# Light-ControllerV3_15.net
KiCad netlist of a schematic drawn in EAGLE
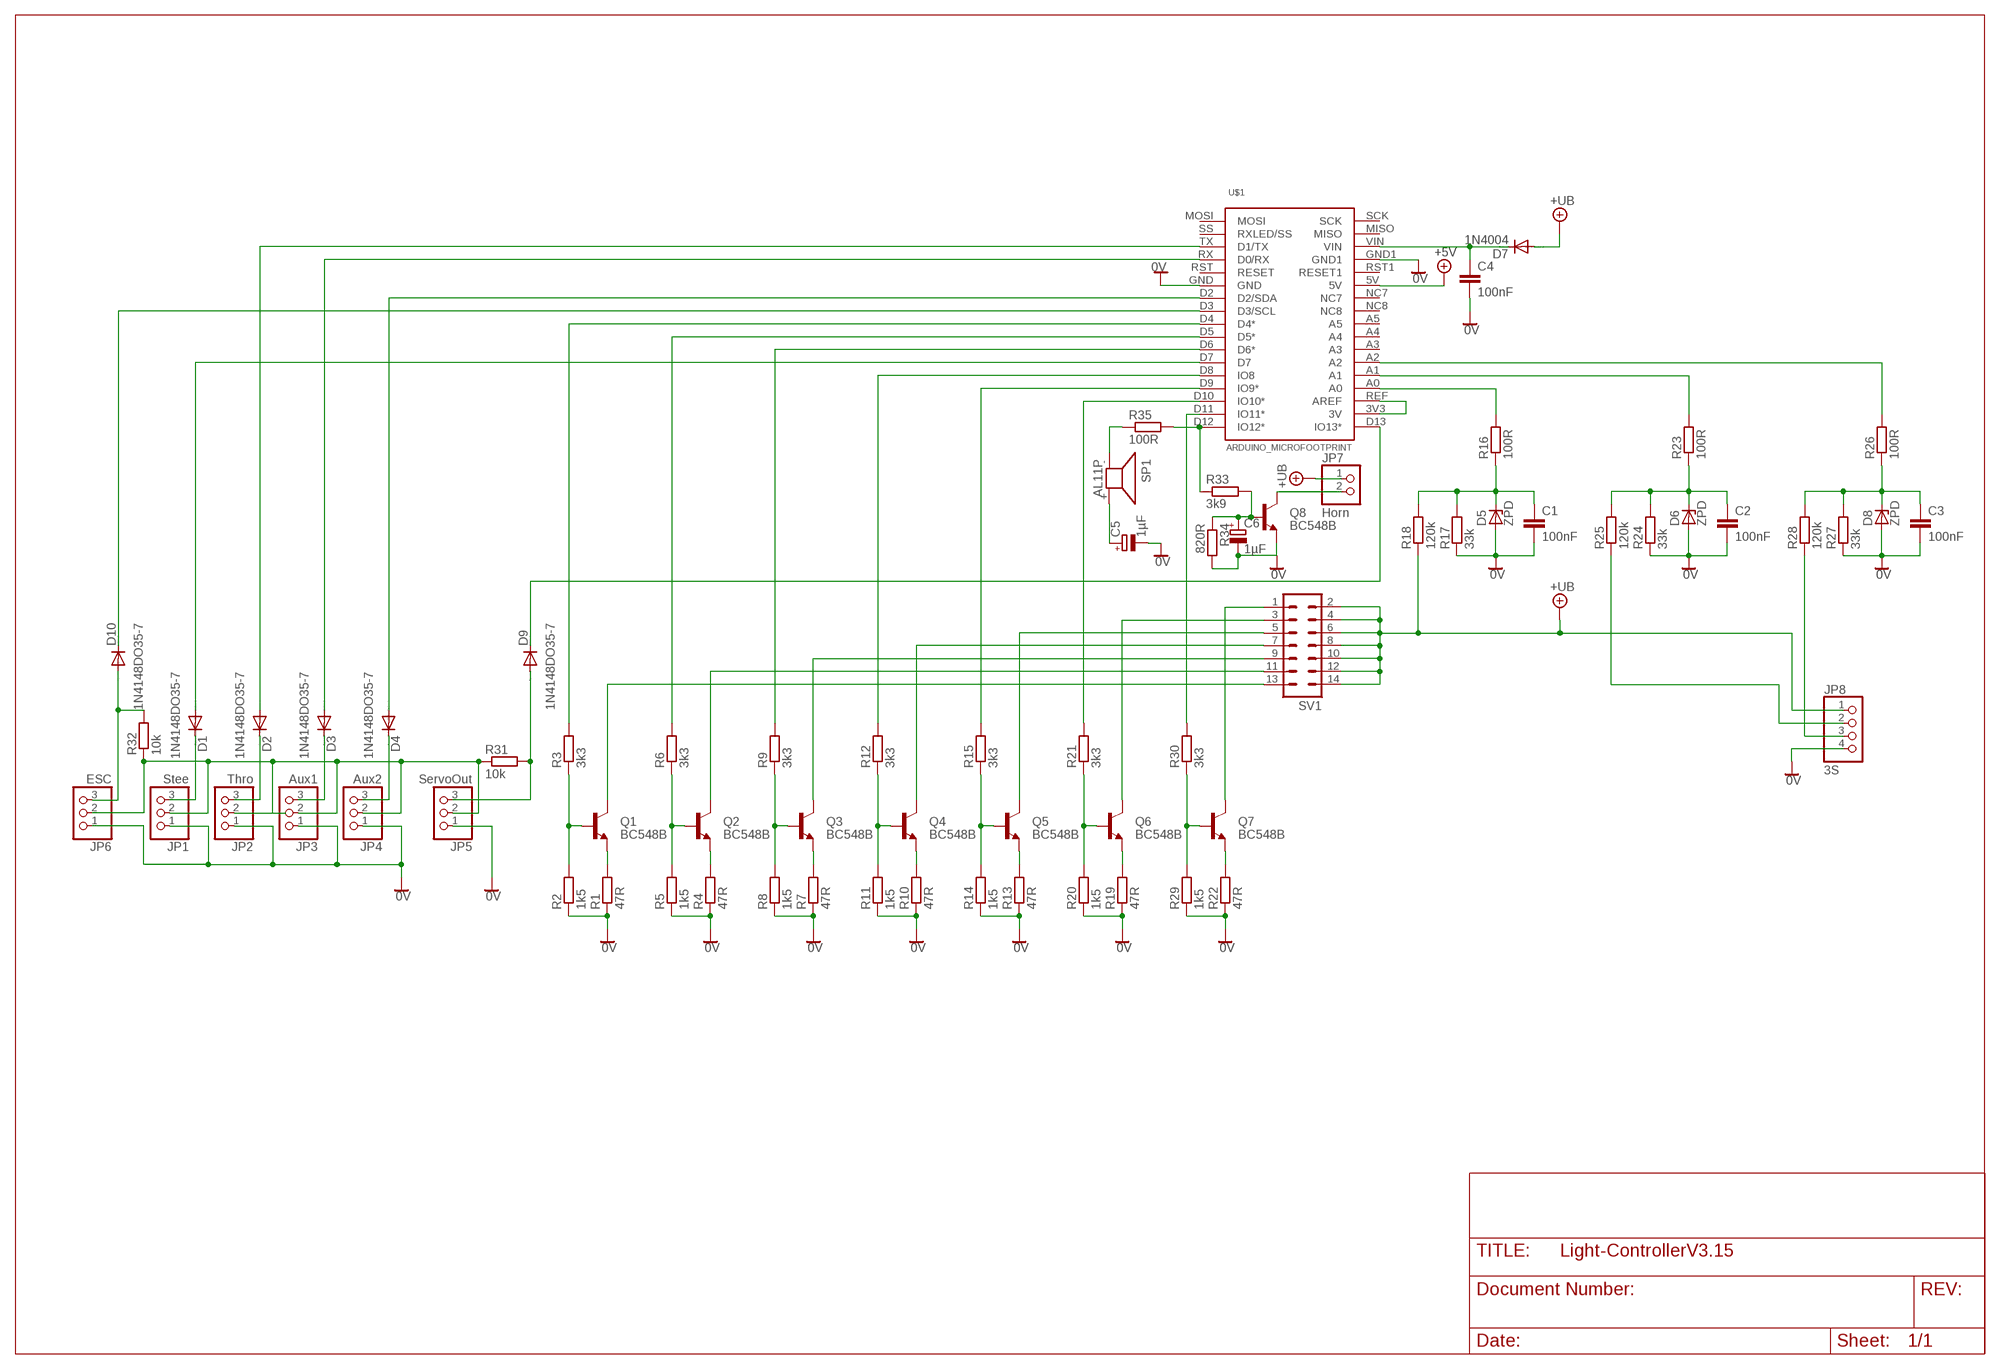
[diagram p0: schematic, sheet 1]

(export (version "E")
  (design (tool "Eeschema 10.0.6"))
  (components
    (comp (ref "C1")
      (value "100nF")
      (footprint "eagle-import:C050-024X044")
      (libsource (lib "eagle-import") (part "C-EU050-024X044"))
    )
    (comp (ref "C2")
      (value "100nF")
      (footprint "eagle-import:C050-024X044")
      (libsource (lib "eagle-import") (part "C-EU050-024X044"))
    )
    (comp (ref "C3")
      (value "100nF")
      (footprint "eagle-import:C050-024X044")
      (libsource (lib "eagle-import") (part "C-EU050-024X044"))
    )
    (comp (ref "C4")
      (value "100nF")
      (footprint "eagle-import:C050-024X044")
      (libsource (lib "eagle-import") (part "C-EU050-024X044"))
    )
    (comp (ref "C5")
      (value "1µF")
      (footprint "eagle-import:E5-4")
      (libsource (lib "eagle-import") (part "CPOL-EUE5-4"))
    )
    (comp (ref "C6")
      (value "1µF")
      (footprint "eagle-import:E2,5-5")
      (libsource (lib "eagle-import") (part "CPOL-EUE2.5-5"))
    )
    (comp (ref "D1")
      (value "1N4148DO35-7")
      (footprint "eagle-import:DO35-7")
      (libsource (lib "eagle-import") (part "1N4148DO35-7"))
    )
    (comp (ref "D2")
      (value "1N4148DO35-7")
      (footprint "eagle-import:DO35-7")
      (libsource (lib "eagle-import") (part "1N4148DO35-7"))
    )
    (comp (ref "D3")
      (value "1N4148DO35-7")
      (footprint "eagle-import:DO35-7")
      (libsource (lib "eagle-import") (part "1N4148DO35-7"))
    )
    (comp (ref "D4")
      (value "1N4148DO35-7")
      (footprint "eagle-import:DO35-7")
      (libsource (lib "eagle-import") (part "1N4148DO35-7"))
    )
    (comp (ref "D5")
      (value "ZPD")
      (footprint "eagle-import:DO35Z10")
      (libsource (lib "eagle-import") (part "ZPD"))
    )
    (comp (ref "D6")
      (value "ZPD")
      (footprint "eagle-import:DO35Z10")
      (libsource (lib "eagle-import") (part "ZPD"))
    )
    (comp (ref "D7")
      (value "1N4004")
      (footprint "eagle-import:DO41-10")
      (libsource (lib "eagle-import") (part "1N4004"))
    )
    (comp (ref "D8")
      (value "ZPD")
      (footprint "eagle-import:DO35Z10")
      (libsource (lib "eagle-import") (part "ZPD"))
    )
    (comp (ref "D9")
      (value "1N4148DO35-7")
      (footprint "eagle-import:DO35-7")
      (libsource (lib "eagle-import") (part "1N4148DO35-7"))
    )
    (comp (ref "D10")
      (value "1N4148DO35-7")
      (footprint "eagle-import:DO35-7")
      (libsource (lib "eagle-import") (part "1N4148DO35-7"))
    )
    (comp (ref "JP1")
      (value "Stee")
      (footprint "eagle-import:1X03")
      (libsource (lib "eagle-import") (part "PINHD-1X3"))
    )
    (comp (ref "JP2")
      (value "Thro")
      (footprint "eagle-import:1X03")
      (libsource (lib "eagle-import") (part "PINHD-1X3"))
    )
    (comp (ref "JP3")
      (value "Aux1")
      (footprint "eagle-import:1X03")
      (libsource (lib "eagle-import") (part "PINHD-1X3"))
    )
    (comp (ref "JP4")
      (value "Aux2")
      (footprint "eagle-import:1X03")
      (libsource (lib "eagle-import") (part "PINHD-1X3"))
    )
    (comp (ref "JP5")
      (value "ServoOut")
      (footprint "eagle-import:1X03")
      (libsource (lib "eagle-import") (part "PINHD-1X3"))
    )
    (comp (ref "JP6")
      (value "ESC")
      (footprint "eagle-import:1X03")
      (libsource (lib "eagle-import") (part "PINHD-1X3"))
    )
    (comp (ref "JP7")
      (value "Horn")
      (footprint "eagle-import:1X02")
      (libsource (lib "eagle-import") (part "PINHD-1X2"))
    )
    (comp (ref "JP8")
      (value "3S")
      (footprint "eagle-import:1X04")
      (libsource (lib "eagle-import") (part "PINHD-1X4"))
    )
    (comp (ref "Q1")
      (value "BC548B")
      (footprint "eagle-import:TO92-EBC")
      (libsource (lib "eagle-import") (part "BC548B"))
    )
    (comp (ref "Q2")
      (value "BC548B")
      (footprint "eagle-import:TO92-EBC")
      (libsource (lib "eagle-import") (part "BC548B"))
    )
    (comp (ref "Q3")
      (value "BC548B")
      (footprint "eagle-import:TO92-EBC")
      (libsource (lib "eagle-import") (part "BC548B"))
    )
    (comp (ref "Q4")
      (value "BC548B")
      (footprint "eagle-import:TO92-EBC")
      (libsource (lib "eagle-import") (part "BC548B"))
    )
    (comp (ref "Q5")
      (value "BC548B")
      (footprint "eagle-import:TO92-EBC")
      (libsource (lib "eagle-import") (part "BC548B"))
    )
    (comp (ref "Q6")
      (value "BC548B")
      (footprint "eagle-import:TO92-EBC")
      (libsource (lib "eagle-import") (part "BC548B"))
    )
    (comp (ref "Q7")
      (value "BC548B")
      (footprint "eagle-import:TO92-EBC")
      (libsource (lib "eagle-import") (part "BC548B"))
    )
    (comp (ref "Q8")
      (value "BC548B")
      (footprint "eagle-import:TO92-EBC")
      (libsource (lib "eagle-import") (part "BC548B"))
    )
    (comp (ref "R1")
      (value "47R")
      (footprint "eagle-import:0204V")
      (libsource (lib "eagle-import") (part "R-EU_0204/2V"))
    )
    (comp (ref "R2")
      (value "1k5")
      (footprint "eagle-import:0204V")
      (libsource (lib "eagle-import") (part "R-EU_0204/2V"))
    )
    (comp (ref "R3")
      (value "3k3")
      (footprint "eagle-import:0204V")
      (libsource (lib "eagle-import") (part "R-EU_0204/2V"))
    )
    (comp (ref "R4")
      (value "47R")
      (footprint "eagle-import:0204V")
      (libsource (lib "eagle-import") (part "R-EU_0204/2V"))
    )
    (comp (ref "R5")
      (value "1k5")
      (footprint "eagle-import:0204V")
      (libsource (lib "eagle-import") (part "R-EU_0204/2V"))
    )
    (comp (ref "R6")
      (value "3k3")
      (footprint "eagle-import:0204V")
      (libsource (lib "eagle-import") (part "R-EU_0204/2V"))
    )
    (comp (ref "R7")
      (value "47R")
      (footprint "eagle-import:0204V")
      (libsource (lib "eagle-import") (part "R-EU_0204/2V"))
    )
    (comp (ref "R8")
      (value "1k5")
      (footprint "eagle-import:0204V")
      (libsource (lib "eagle-import") (part "R-EU_0204/2V"))
    )
    (comp (ref "R9")
      (value "3k3")
      (footprint "eagle-import:0204V")
      (libsource (lib "eagle-import") (part "R-EU_0204/2V"))
    )
    (comp (ref "R10")
      (value "47R")
      (footprint "eagle-import:0204V")
      (libsource (lib "eagle-import") (part "R-EU_0204/2V"))
    )
    (comp (ref "R11")
      (value "1k5")
      (footprint "eagle-import:0204V")
      (libsource (lib "eagle-import") (part "R-EU_0204/2V"))
    )
    (comp (ref "R12")
      (value "3k3")
      (footprint "eagle-import:0204V")
      (libsource (lib "eagle-import") (part "R-EU_0204/2V"))
    )
    (comp (ref "R13")
      (value "47R")
      (footprint "eagle-import:0204V")
      (libsource (lib "eagle-import") (part "R-EU_0204/2V"))
    )
    (comp (ref "R14")
      (value "1k5")
      (footprint "eagle-import:0204V")
      (libsource (lib "eagle-import") (part "R-EU_0204/2V"))
    )
    (comp (ref "R15")
      (value "3k3")
      (footprint "eagle-import:0204V")
      (libsource (lib "eagle-import") (part "R-EU_0204/2V"))
    )
    (comp (ref "R16")
      (value "100R")
      (footprint "eagle-import:0204_7")
      (libsource (lib "eagle-import") (part "R-EU_0204/7"))
    )
    (comp (ref "R17")
      (value "33k")
      (footprint "eagle-import:0204_7")
      (libsource (lib "eagle-import") (part "R-EU_0204/7"))
    )
    (comp (ref "R18")
      (value "120k")
      (footprint "eagle-import:0204_7")
      (libsource (lib "eagle-import") (part "R-EU_0204/7"))
    )
    (comp (ref "R19")
      (value "47R")
      (footprint "eagle-import:0204V")
      (libsource (lib "eagle-import") (part "R-EU_0204/2V"))
    )
    (comp (ref "R20")
      (value "1k5")
      (footprint "eagle-import:0204V")
      (libsource (lib "eagle-import") (part "R-EU_0204/2V"))
    )
    (comp (ref "R21")
      (value "3k3")
      (footprint "eagle-import:0204V")
      (libsource (lib "eagle-import") (part "R-EU_0204/2V"))
    )
    (comp (ref "R22")
      (value "47R")
      (footprint "eagle-import:0204V")
      (libsource (lib "eagle-import") (part "R-EU_0204/2V"))
    )
    (comp (ref "R23")
      (value "100R")
      (footprint "eagle-import:0204_7")
      (libsource (lib "eagle-import") (part "R-EU_0204/7"))
    )
    (comp (ref "R24")
      (value "33k")
      (footprint "eagle-import:0204_7")
      (libsource (lib "eagle-import") (part "R-EU_0204/7"))
    )
    (comp (ref "R25")
      (value "120k")
      (footprint "eagle-import:0204_7")
      (libsource (lib "eagle-import") (part "R-EU_0204/7"))
    )
    (comp (ref "R26")
      (value "100R")
      (footprint "eagle-import:0204_7")
      (libsource (lib "eagle-import") (part "R-EU_0204/7"))
    )
    (comp (ref "R27")
      (value "33k")
      (footprint "eagle-import:0204_7")
      (libsource (lib "eagle-import") (part "R-EU_0204/7"))
    )
    (comp (ref "R28")
      (value "120k")
      (footprint "eagle-import:0204_7")
      (libsource (lib "eagle-import") (part "R-EU_0204/7"))
    )
    (comp (ref "R29")
      (value "1k5")
      (footprint "eagle-import:0204V")
      (libsource (lib "eagle-import") (part "R-EU_0204/2V"))
    )
    (comp (ref "R30")
      (value "3k3")
      (footprint "eagle-import:0204V")
      (libsource (lib "eagle-import") (part "R-EU_0204/2V"))
    )
    (comp (ref "R31")
      (value "10k")
      (footprint "eagle-import:0204V")
      (libsource (lib "eagle-import") (part "R-EU_0204/2V"))
    )
    (comp (ref "R32")
      (value "10k")
      (footprint "eagle-import:0204V")
      (libsource (lib "eagle-import") (part "R-EU_0204/2V"))
    )
    (comp (ref "R33")
      (value "3k9")
      (footprint "eagle-import:0204_7")
      (libsource (lib "eagle-import") (part "R-EU_0204/7"))
    )
    (comp (ref "R34")
      (value "820R")
      (footprint "eagle-import:0204_7")
      (libsource (lib "eagle-import") (part "R-EU_0204/7"))
    )
    (comp (ref "R35")
      (value "100R")
      (footprint "eagle-import:0204_7")
      (libsource (lib "eagle-import") (part "R-EU_0204/7"))
    )
    (comp (ref "SP1")
      (value "AL11P")
      (footprint "eagle-import:AL11P")
      (libsource (lib "eagle-import") (part "AL11P"))
    )
    (comp (ref "SV1")
      (value "ML14")
      (footprint "eagle-import:ML14")
      (libsource (lib "eagle-import") (part "ML14"))
    )
    (comp (ref "U$1")
      (value "ARDUINO_MICROFOOTPRINT")
      (footprint "eagle-import:ARDUINO-MICRO")
      (libsource (lib "eagle-import") (part "ARDUINO_MICROFOOTPRINT"))
    )
  )
  (nets
    (net (code "1") (name "+5V") (class "Default")
      (node (ref "U$1") (pin "5V") (pinfunction "5V_5V") (pintype "bidirectional"))
    )
    (net (code "2") (name "+UB") (class "Default")
      (node (ref "D7") (pin "A") (pinfunction "A_A") (pintype "passive"))
      (node (ref "JP7") (pin "1") (pinfunction "1_1") (pintype "passive"))
      (node (ref "JP8") (pin "1") (pinfunction "1_1") (pintype "passive"))
      (node (ref "R18") (pin "1") (pinfunction "1_1") (pintype "passive"))
      (node (ref "SV1") (pin "10") (pinfunction "10_10") (pintype "passive"))
      (node (ref "SV1") (pin "12") (pinfunction "12_12") (pintype "passive"))
      (node (ref "SV1") (pin "14") (pinfunction "14_14") (pintype "passive"))
      (node (ref "SV1") (pin "2") (pinfunction "2_2") (pintype "passive"))
      (node (ref "SV1") (pin "4") (pinfunction "4_4") (pintype "passive"))
      (node (ref "SV1") (pin "6") (pinfunction "6_6") (pintype "passive"))
      (node (ref "SV1") (pin "8") (pinfunction "8_8") (pintype "passive"))
    )
    (net (code "3") (name "0V") (class "Default")
      (node (ref "C1") (pin "2") (pinfunction "2_2") (pintype "passive"))
      (node (ref "C2") (pin "2") (pinfunction "2_2") (pintype "passive"))
      (node (ref "C3") (pin "2") (pinfunction "2_2") (pintype "passive"))
      (node (ref "C4") (pin "2") (pinfunction "2_2") (pintype "passive"))
      (node (ref "C5") (pin "-") (pinfunction "-_-") (pintype "passive"))
      (node (ref "C6") (pin "-") (pinfunction "-_-") (pintype "passive"))
      (node (ref "D5") (pin "A") (pinfunction "A_A") (pintype "passive"))
      (node (ref "D6") (pin "A") (pinfunction "A_A") (pintype "passive"))
      (node (ref "D8") (pin "A") (pinfunction "A_A") (pintype "passive"))
      (node (ref "JP1") (pin "1") (pinfunction "1_1") (pintype "passive"))
      (node (ref "JP2") (pin "1") (pinfunction "1_1") (pintype "passive"))
      (node (ref "JP3") (pin "1") (pinfunction "1_1") (pintype "passive"))
      (node (ref "JP4") (pin "1") (pinfunction "1_1") (pintype "passive"))
      (node (ref "JP5") (pin "1") (pinfunction "1_1") (pintype "passive"))
      (node (ref "JP6") (pin "1") (pinfunction "1_1") (pintype "passive"))
      (node (ref "JP8") (pin "4") (pinfunction "4_4") (pintype "passive"))
      (node (ref "Q8") (pin "E") (pinfunction "E_E") (pintype "passive"))
      (node (ref "R1") (pin "1") (pinfunction "1_1") (pintype "passive"))
      (node (ref "R10") (pin "1") (pinfunction "1_1") (pintype "passive"))
      (node (ref "R11") (pin "1") (pinfunction "1_1") (pintype "passive"))
      (node (ref "R13") (pin "1") (pinfunction "1_1") (pintype "passive"))
      (node (ref "R14") (pin "1") (pinfunction "1_1") (pintype "passive"))
      (node (ref "R17") (pin "1") (pinfunction "1_1") (pintype "passive"))
      (node (ref "R19") (pin "1") (pinfunction "1_1") (pintype "passive"))
      (node (ref "R2") (pin "1") (pinfunction "1_1") (pintype "passive"))
      (node (ref "R20") (pin "1") (pinfunction "1_1") (pintype "passive"))
      (node (ref "R22") (pin "1") (pinfunction "1_1") (pintype "passive"))
      (node (ref "R24") (pin "1") (pinfunction "1_1") (pintype "passive"))
      (node (ref "R27") (pin "1") (pinfunction "1_1") (pintype "passive"))
      (node (ref "R29") (pin "1") (pinfunction "1_1") (pintype "passive"))
      (node (ref "R34") (pin "2") (pinfunction "2_2") (pintype "passive"))
      (node (ref "R4") (pin "1") (pinfunction "1_1") (pintype "passive"))
      (node (ref "R5") (pin "1") (pinfunction "1_1") (pintype "passive"))
      (node (ref "R7") (pin "1") (pinfunction "1_1") (pintype "passive"))
      (node (ref "R8") (pin "1") (pinfunction "1_1") (pintype "passive"))
      (node (ref "U$1") (pin "GND") (pinfunction "GND_GND") (pintype "bidirectional"))
      (node (ref "U$1") (pin "GND1") (pinfunction "GND1_GND1") (pintype "bidirectional"))
    )
    (net (code "4") (name "Net-(C1-Pad1)") (class "Default")
      (node (ref "C1") (pin "1") (pinfunction "1_1") (pintype "passive"))
      (node (ref "D5") (pin "C") (pinfunction "C_C") (pintype "passive"))
      (node (ref "R16") (pin "1") (pinfunction "1_1") (pintype "passive"))
      (node (ref "R17") (pin "2") (pinfunction "2_2") (pintype "passive"))
      (node (ref "R18") (pin "2") (pinfunction "2_2") (pintype "passive"))
    )
    (net (code "5") (name "Net-(C2-Pad1)") (class "Default")
      (node (ref "C2") (pin "1") (pinfunction "1_1") (pintype "passive"))
      (node (ref "D6") (pin "C") (pinfunction "C_C") (pintype "passive"))
      (node (ref "R23") (pin "1") (pinfunction "1_1") (pintype "passive"))
      (node (ref "R24") (pin "2") (pinfunction "2_2") (pintype "passive"))
      (node (ref "R25") (pin "2") (pinfunction "2_2") (pintype "passive"))
    )
    (net (code "6") (name "Net-(C3-Pad1)") (class "Default")
      (node (ref "C3") (pin "1") (pinfunction "1_1") (pintype "passive"))
      (node (ref "D8") (pin "C") (pinfunction "C_C") (pintype "passive"))
      (node (ref "R26") (pin "1") (pinfunction "1_1") (pintype "passive"))
      (node (ref "R27") (pin "2") (pinfunction "2_2") (pintype "passive"))
      (node (ref "R28") (pin "2") (pinfunction "2_2") (pintype "passive"))
    )
    (net (code "7") (name "Net-(C4-Pad1)") (class "Default")
      (node (ref "C4") (pin "1") (pinfunction "1_1") (pintype "passive"))
      (node (ref "D7") (pin "C") (pinfunction "C_C") (pintype "passive"))
      (node (ref "U$1") (pin "VIN") (pinfunction "VIN_VIN") (pintype "bidirectional"))
    )
    (net (code "8") (name "Net-(C6-Pad+)") (class "Default")
      (node (ref "C6") (pin "+") (pinfunction "+_+") (pintype "passive"))
      (node (ref "Q8") (pin "B") (pinfunction "B_B") (pintype "passive"))
      (node (ref "R33") (pin "2") (pinfunction "2_2") (pintype "passive"))
      (node (ref "R34") (pin "1") (pinfunction "1_1") (pintype "passive"))
    )
    (net (code "9") (name "Net-(D1-PadA)") (class "Default")
      (node (ref "D1") (pin "A") (pinfunction "A_A") (pintype "passive"))
      (node (ref "U$1") (pin "D7") (pinfunction "D7_D7") (pintype "bidirectional"))
    )
    (net (code "10") (name "Net-(D1-PadC)") (class "Default")
      (node (ref "D1") (pin "C") (pinfunction "C_C") (pintype "passive"))
      (node (ref "JP1") (pin "3") (pinfunction "3_3") (pintype "passive"))
    )
    (net (code "11") (name "Net-(D2-PadC)") (class "Default")
      (node (ref "D2") (pin "C") (pinfunction "C_C") (pintype "passive"))
      (node (ref "JP2") (pin "3") (pinfunction "3_3") (pintype "passive"))
    )
    (net (code "12") (name "Net-(D3-PadC)") (class "Default")
      (node (ref "D3") (pin "C") (pinfunction "C_C") (pintype "passive"))
      (node (ref "JP3") (pin "3") (pinfunction "3_3") (pintype "passive"))
    )
    (net (code "13") (name "Net-(D4-PadC)") (class "Default")
      (node (ref "D4") (pin "C") (pinfunction "C_C") (pintype "passive"))
      (node (ref "JP4") (pin "3") (pinfunction "3_3") (pintype "passive"))
    )
    (net (code "14") (name "Net-(D9-PadA)") (class "Default")
      (node (ref "D9") (pin "A") (pinfunction "A_A") (pintype "passive"))
      (node (ref "JP5") (pin "3") (pinfunction "3_3") (pintype "passive"))
      (node (ref "R31") (pin "2") (pinfunction "2_2") (pintype "passive"))
    )
    (net (code "15") (name "Net-(D10-PadA)") (class "Default")
      (node (ref "D10") (pin "A") (pinfunction "A_A") (pintype "passive"))
      (node (ref "JP6") (pin "3") (pinfunction "3_3") (pintype "passive"))
      (node (ref "R32") (pin "2") (pinfunction "2_2") (pintype "passive"))
    )
    (net (code "16") (name "Net-(JP1-Pad2)") (class "Default")
      (node (ref "JP1") (pin "2") (pinfunction "2_2") (pintype "passive"))
      (node (ref "JP2") (pin "2") (pinfunction "2_2") (pintype "passive"))
      (node (ref "JP3") (pin "2") (pinfunction "2_2") (pintype "passive"))
      (node (ref "JP4") (pin "2") (pinfunction "2_2") (pintype "passive"))
      (node (ref "JP5") (pin "2") (pinfunction "2_2") (pintype "passive"))
      (node (ref "JP6") (pin "2") (pinfunction "2_2") (pintype "passive"))
      (node (ref "R31") (pin "1") (pinfunction "1_1") (pintype "passive"))
      (node (ref "R32") (pin "1") (pinfunction "1_1") (pintype "passive"))
    )
    (net (code "17") (name "Net-(JP7-Pad2)") (class "Default")
      (node (ref "JP7") (pin "2") (pinfunction "2_2") (pintype "passive"))
      (node (ref "Q8") (pin "C") (pinfunction "C_C") (pintype "passive"))
    )
    (net (code "18") (name "Net-(JP8-Pad2)") (class "Default")
      (node (ref "JP8") (pin "2") (pinfunction "2_2") (pintype "passive"))
      (node (ref "R25") (pin "1") (pinfunction "1_1") (pintype "passive"))
    )
    (net (code "19") (name "Net-(JP8-Pad3)") (class "Default")
      (node (ref "JP8") (pin "3") (pinfunction "3_3") (pintype "passive"))
      (node (ref "R28") (pin "1") (pinfunction "1_1") (pintype "passive"))
    )
    (net (code "20") (name "Net-(Q1-PadB)") (class "Default")
      (node (ref "Q1") (pin "B") (pinfunction "B_B") (pintype "passive"))
      (node (ref "R2") (pin "2") (pinfunction "2_2") (pintype "passive"))
      (node (ref "R3") (pin "1") (pinfunction "1_1") (pintype "passive"))
    )
    (net (code "21") (name "Net-(Q1-PadC)") (class "Default")
      (node (ref "Q1") (pin "C") (pinfunction "C_C") (pintype "passive"))
      (node (ref "SV1") (pin "13") (pinfunction "13_13") (pintype "passive"))
    )
    (net (code "22") (name "Net-(Q1-PadE)") (class "Default")
      (node (ref "Q1") (pin "E") (pinfunction "E_E") (pintype "passive"))
      (node (ref "R1") (pin "2") (pinfunction "2_2") (pintype "passive"))
    )
    (net (code "23") (name "Net-(Q2-PadB)") (class "Default")
      (node (ref "Q2") (pin "B") (pinfunction "B_B") (pintype "passive"))
      (node (ref "R5") (pin "2") (pinfunction "2_2") (pintype "passive"))
      (node (ref "R6") (pin "1") (pinfunction "1_1") (pintype "passive"))
    )
    (net (code "24") (name "Net-(Q2-PadC)") (class "Default")
      (node (ref "Q2") (pin "C") (pinfunction "C_C") (pintype "passive"))
      (node (ref "SV1") (pin "11") (pinfunction "11_11") (pintype "passive"))
    )
    (net (code "25") (name "Net-(Q2-PadE)") (class "Default")
      (node (ref "Q2") (pin "E") (pinfunction "E_E") (pintype "passive"))
      (node (ref "R4") (pin "2") (pinfunction "2_2") (pintype "passive"))
    )
    (net (code "26") (name "Net-(Q3-PadB)") (class "Default")
      (node (ref "Q3") (pin "B") (pinfunction "B_B") (pintype "passive"))
      (node (ref "R8") (pin "2") (pinfunction "2_2") (pintype "passive"))
      (node (ref "R9") (pin "1") (pinfunction "1_1") (pintype "passive"))
    )
    (net (code "27") (name "Net-(Q3-PadC)") (class "Default")
      (node (ref "Q3") (pin "C") (pinfunction "C_C") (pintype "passive"))
      (node (ref "SV1") (pin "9") (pinfunction "9_9") (pintype "passive"))
    )
    (net (code "28") (name "Net-(Q3-PadE)") (class "Default")
      (node (ref "Q3") (pin "E") (pinfunction "E_E") (pintype "passive"))
      (node (ref "R7") (pin "2") (pinfunction "2_2") (pintype "passive"))
    )
    (net (code "29") (name "Net-(Q4-PadB)") (class "Default")
      (node (ref "Q4") (pin "B") (pinfunction "B_B") (pintype "passive"))
      (node (ref "R11") (pin "2") (pinfunction "2_2") (pintype "passive"))
      (node (ref "R12") (pin "1") (pinfunction "1_1") (pintype "passive"))
    )
    (net (code "30") (name "Net-(Q4-PadC)") (class "Default")
      (node (ref "Q4") (pin "C") (pinfunction "C_C") (pintype "passive"))
      (node (ref "SV1") (pin "7") (pinfunction "7_7") (pintype "passive"))
    )
    (net (code "31") (name "Net-(Q4-PadE)") (class "Default")
      (node (ref "Q4") (pin "E") (pinfunction "E_E") (pintype "passive"))
      (node (ref "R10") (pin "2") (pinfunction "2_2") (pintype "passive"))
    )
    (net (code "32") (name "Net-(Q5-PadB)") (class "Default")
      (node (ref "Q5") (pin "B") (pinfunction "B_B") (pintype "passive"))
      (node (ref "R14") (pin "2") (pinfunction "2_2") (pintype "passive"))
      (node (ref "R15") (pin "1") (pinfunction "1_1") (pintype "passive"))
    )
    (net (code "33") (name "Net-(Q5-PadC)") (class "Default")
      (node (ref "Q5") (pin "C") (pinfunction "C_C") (pintype "passive"))
      (node (ref "SV1") (pin "5") (pinfunction "5_5") (pintype "passive"))
    )
    (net (code "34") (name "Net-(Q5-PadE)") (class "Default")
      (node (ref "Q5") (pin "E") (pinfunction "E_E") (pintype "passive"))
      (node (ref "R13") (pin "2") (pinfunction "2_2") (pintype "passive"))
    )
    (net (code "35") (name "Net-(Q6-PadB)") (class "Default")
      (node (ref "Q6") (pin "B") (pinfunction "B_B") (pintype "passive"))
      (node (ref "R20") (pin "2") (pinfunction "2_2") (pintype "passive"))
      (node (ref "R21") (pin "1") (pinfunction "1_1") (pintype "passive"))
    )
    (net (code "36") (name "Net-(Q6-PadC)") (class "Default")
      (node (ref "Q6") (pin "C") (pinfunction "C_C") (pintype "passive"))
      (node (ref "SV1") (pin "3") (pinfunction "3_3") (pintype "passive"))
    )
    (net (code "37") (name "Net-(Q6-PadE)") (class "Default")
      (node (ref "Q6") (pin "E") (pinfunction "E_E") (pintype "passive"))
      (node (ref "R19") (pin "2") (pinfunction "2_2") (pintype "passive"))
    )
    (net (code "38") (name "Net-(Q7-PadB)") (class "Default")
      (node (ref "Q7") (pin "B") (pinfunction "B_B") (pintype "passive"))
      (node (ref "R29") (pin "2") (pinfunction "2_2") (pintype "passive"))
      (node (ref "R30") (pin "1") (pinfunction "1_1") (pintype "passive"))
    )
    (net (code "39") (name "Net-(Q7-PadC)") (class "Default")
      (node (ref "Q7") (pin "C") (pinfunction "C_C") (pintype "passive"))
      (node (ref "SV1") (pin "1") (pinfunction "1_1") (pintype "passive"))
    )
    (net (code "40") (name "Net-(Q7-PadE)") (class "Default")
      (node (ref "Q7") (pin "E") (pinfunction "E_E") (pintype "passive"))
      (node (ref "R22") (pin "2") (pinfunction "2_2") (pintype "passive"))
    )
    (net (code "41") (name "Net-(R16-Pad2)") (class "Default")
      (node (ref "R16") (pin "2") (pinfunction "2_2") (pintype "passive"))
      (node (ref "U$1") (pin "A0") (pinfunction "A0_A0") (pintype "bidirectional"))
    )
    (net (code "42") (name "Net-(R23-Pad2)") (class "Default")
      (node (ref "R23") (pin "2") (pinfunction "2_2") (pintype "passive"))
      (node (ref "U$1") (pin "A1") (pinfunction "A1_A1") (pintype "bidirectional"))
    )
    (net (code "43") (name "Net-(R26-Pad2)") (class "Default")
      (node (ref "R26") (pin "2") (pinfunction "2_2") (pintype "passive"))
      (node (ref "U$1") (pin "A2") (pinfunction "A2_A2") (pintype "bidirectional"))
    )
    (net (code "44") (name "Net-(SP1-1)") (class "Default")
      (node (ref "R35") (pin "1") (pinfunction "1_1") (pintype "passive"))
      (node (ref "SP1") (pin "-") (pinfunction "1_-") (pintype "passive"))
    )
    (net (code "45") (name "Net-(SP1-2)") (class "Default")
      (node (ref "C5") (pin "+") (pinfunction "+_+") (pintype "passive"))
      (node (ref "SP1") (pin "+") (pinfunction "2_+") (pintype "passive"))
    )
    (net (code "46") (name "Net-(U$1-3V)") (class "Default")
      (node (ref "U$1") (pin "3V3") (pinfunction "3V_3V3") (pintype "bidirectional"))
      (node (ref "U$1") (pin "REF") (pinfunction "AREF_REF") (pintype "bidirectional"))
    )
    (net (code "47") (name "Net-(U$1-D0{slash}RX)") (class "Default")
      (node (ref "D3") (pin "A") (pinfunction "A_A") (pintype "passive"))
      (node (ref "U$1") (pin "RX") (pinfunction "D0/RX_RX") (pintype "bidirectional"))
    )
    (net (code "48") (name "Net-(U$1-D1{slash}TX)") (class "Default")
      (node (ref "D2") (pin "A") (pinfunction "A_A") (pintype "passive"))
      (node (ref "U$1") (pin "TX") (pinfunction "D1/TX_TX") (pintype "bidirectional"))
    )
    (net (code "49") (name "Net-(U$1-D2{slash}SDA)") (class "Default")
      (node (ref "D4") (pin "A") (pinfunction "A_A") (pintype "passive"))
      (node (ref "U$1") (pin "D2") (pinfunction "D2/SDA_D2") (pintype "bidirectional"))
    )
    (net (code "50") (name "Net-(U$1-D3{slash}SCL)") (class "Default")
      (node (ref "D10") (pin "C") (pinfunction "C_C") (pintype "passive"))
      (node (ref "U$1") (pin "D3") (pinfunction "D3/SCL_D3") (pintype "bidirectional"))
    )
    (net (code "51") (name "Net-(U$1-D4*)") (class "Default")
      (node (ref "R3") (pin "2") (pinfunction "2_2") (pintype "passive"))
      (node (ref "U$1") (pin "D4") (pinfunction "D4*_D4") (pintype "bidirectional"))
    )
    (net (code "52") (name "Net-(U$1-D5*)") (class "Default")
      (node (ref "R6") (pin "2") (pinfunction "2_2") (pintype "passive"))
      (node (ref "U$1") (pin "D5") (pinfunction "D5*_D5") (pintype "bidirectional"))
    )
    (net (code "53") (name "Net-(U$1-D6*)") (class "Default")
      (node (ref "R9") (pin "2") (pinfunction "2_2") (pintype "passive"))
      (node (ref "U$1") (pin "D6") (pinfunction "D6*_D6") (pintype "bidirectional"))
    )
    (net (code "54") (name "Net-(U$1-IO8)") (class "Default")
      (node (ref "R12") (pin "2") (pinfunction "2_2") (pintype "passive"))
      (node (ref "U$1") (pin "D8") (pinfunction "IO8_D8") (pintype "bidirectional"))
    )
    (net (code "55") (name "Net-(U$1-IO9*)") (class "Default")
      (node (ref "R15") (pin "2") (pinfunction "2_2") (pintype "passive"))
      (node (ref "U$1") (pin "D9") (pinfunction "IO9*_D9") (pintype "bidirectional"))
    )
    (net (code "56") (name "Net-(U$1-IO10*)") (class "Default")
      (node (ref "R21") (pin "2") (pinfunction "2_2") (pintype "passive"))
      (node (ref "U$1") (pin "D10") (pinfunction "IO10*_D10") (pintype "bidirectional"))
    )
    (net (code "57") (name "Net-(U$1-IO11*)") (class "Default")
      (node (ref "R30") (pin "2") (pinfunction "2_2") (pintype "passive"))
      (node (ref "U$1") (pin "D11") (pinfunction "IO11*_D11") (pintype "bidirectional"))
    )
    (net (code "58") (name "Net-(U$1-IO12*)") (class "Default")
      (node (ref "R33") (pin "1") (pinfunction "1_1") (pintype "passive"))
      (node (ref "R35") (pin "2") (pinfunction "2_2") (pintype "passive"))
      (node (ref "U$1") (pin "D12") (pinfunction "IO12*_D12") (pintype "bidirectional"))
    )
    (net (code "59") (name "Net-(U$1-IO13*)") (class "Default")
      (node (ref "D9") (pin "C") (pinfunction "C_C") (pintype "passive"))
      (node (ref "U$1") (pin "D13") (pinfunction "IO13*_D13") (pintype "bidirectional"))
    )
    (net (code "60") (name "unconnected-(U$1-PadA3)") (class "Default")
      (node (ref "U$1") (pin "A3") (pinfunction "A3_A3") (pintype "bidirectional"))
    )
    (net (code "61") (name "unconnected-(U$1-PadA4)") (class "Default")
      (node (ref "U$1") (pin "A4") (pinfunction "A4_A4") (pintype "bidirectional"))
    )
    (net (code "62") (name "unconnected-(U$1-PadA5)") (class "Default")
      (node (ref "U$1") (pin "A5") (pinfunction "A5_A5") (pintype "bidirectional"))
    )
    (net (code "63") (name "unconnected-(U$1-PadMISO)") (class "Default")
      (node (ref "U$1") (pin "MISO") (pinfunction "MISO_MISO") (pintype "bidirectional"))
    )
    (net (code "64") (name "unconnected-(U$1-PadMOSI)") (class "Default")
      (node (ref "U$1") (pin "MOSI") (pinfunction "MOSI_MOSI") (pintype "bidirectional"))
    )
    (net (code "65") (name "unconnected-(U$1-PadNC7)") (class "Default")
      (node (ref "U$1") (pin "NC7") (pinfunction "NC7_NC7") (pintype "bidirectional"))
    )
    (net (code "66") (name "unconnected-(U$1-PadNC8)") (class "Default")
      (node (ref "U$1") (pin "NC8") (pinfunction "NC8_NC8") (pintype "bidirectional"))
    )
    (net (code "67") (name "unconnected-(U$1-PadSCK)") (class "Default")
      (node (ref "U$1") (pin "SCK") (pinfunction "SCK_SCK") (pintype "bidirectional"))
    )
    (net (code "68") (name "unconnected-(U$1-RESET-PadRST)") (class "Default")
      (node (ref "U$1") (pin "RST") (pinfunction "RESET_RST") (pintype "bidirectional"))
    )
    (net (code "69") (name "unconnected-(U$1-RESET1-PadRST1)") (class "Default")
      (node (ref "U$1") (pin "RST1") (pinfunction "RESET1_RST1") (pintype "bidirectional"))
    )
    (net (code "70") (name "unconnected-(U$1-RXLED{slash}SS-PadSS)") (class "Default")
      (node (ref "U$1") (pin "SS") (pinfunction "RXLED/SS_SS") (pintype "bidirectional"))
    )
  )
)
